# Zio_Qwiic_PM2_5_Sensor_Adapter.net
KiCad netlist of a schematic drawn in EAGLE
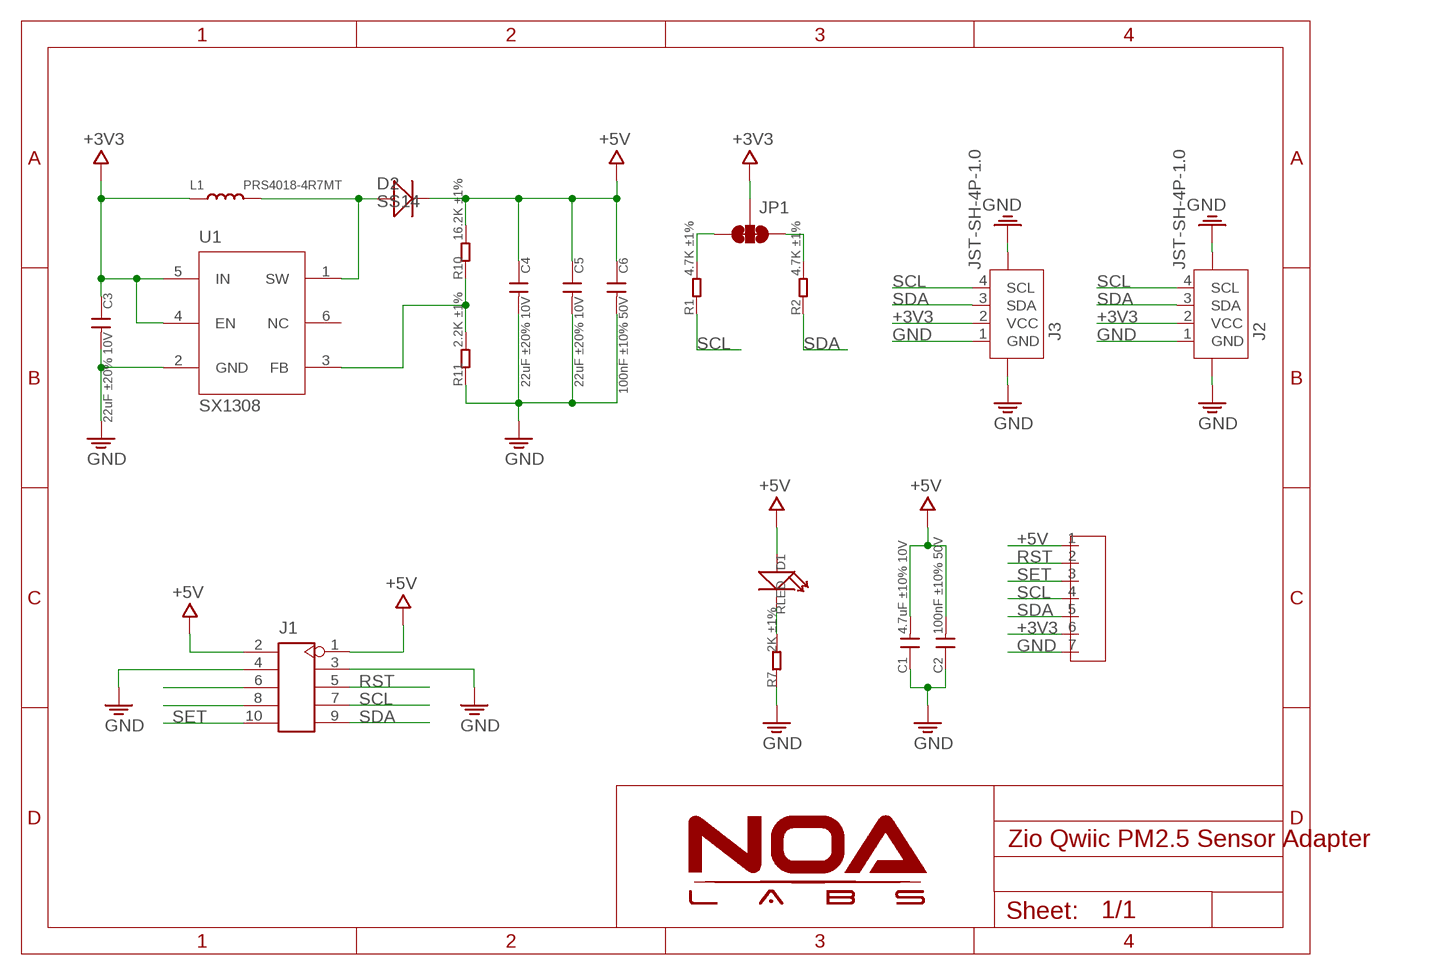
[diagram p0: schematic, sheet 1]

(export (version "E")
  (design (tool "Eeschema 10.0.6"))
  (components
    (comp (ref "C1")
      (value "4.7uF ±10% 10V")
      (footprint "eagle-import:C0603")
      (libsource (lib "eagle-import") (part "C-0603"))
    )
    (comp (ref "C2")
      (value "100nF ±10% 50V")
      (footprint "eagle-import:C0603")
      (libsource (lib "eagle-import") (part "C-0603"))
    )
    (comp (ref "C3")
      (value "22uF ±20% 10V")
      (footprint "eagle-import:C0805")
      (libsource (lib "eagle-import") (part "C-0805"))
    )
    (comp (ref "C4")
      (value "22uF ±20% 10V")
      (footprint "eagle-import:C0805")
      (libsource (lib "eagle-import") (part "C-0805"))
    )
    (comp (ref "C5")
      (value "22uF ±20% 10V")
      (footprint "eagle-import:C0805")
      (libsource (lib "eagle-import") (part "C-0805"))
    )
    (comp (ref "C6")
      (value "100nF ±10% 50V")
      (footprint "eagle-import:C0603")
      (libsource (lib "eagle-import") (part "C-0603"))
    )
    (comp (ref "D1")
      (value "RLED")
      (footprint "eagle-import:LED-0603")
      (libsource (lib "eagle-import") (part "LED'0603'"))
    )
    (comp (ref "D2")
      (value "SS14")
      (footprint "eagle-import:DO-214AC")
      (libsource (lib "eagle-import") (part "D214AA"))
    )
    (comp (ref "J1")
      (value "HEADER-2X5P-PM2.5")
      (footprint "eagle-import:2X5P-1.27-THT-PM2.5")
      (libsource (lib "eagle-import") (part "HEADER-2X5P-PM2.5"))
    )
    (comp (ref "J2")
      (value "JST-SH-4P-1.0")
      (footprint "eagle-import:JST-SH-4P")
      (libsource (lib "eagle-import") (part "JST-SH-4P-1.0"))
    )
    (comp (ref "J3")
      (value "JST-SH-4P-1.0")
      (footprint "eagle-import:JST-SH-4P")
      (libsource (lib "eagle-import") (part "JST-SH-4P-1.0"))
    )
    (comp (ref "J5")
      (value "HEADER-7P")
      (footprint "eagle-import:7P-2.54-60_35MIL")
      (libsource (lib "eagle-import") (part "HEADER-7P"))
    )
    (comp (ref "JP1")
      (value "SMT-JUMPER_3_2-NC_TRACE")
      (footprint "eagle-import:SMT-JUMPER_3_2-NC_TRACE")
      (libsource (lib "eagle-import") (part "SMT-JUMPER_3_2-NC_TRACE"))
    )
    (comp (ref "L1")
      (value "PRS4018-4R7MT")
      (footprint "eagle-import:L4030")
      (libsource (lib "eagle-import") (part "L-4030"))
    )
    (comp (ref "R1")
      (value "4.7K ±1%")
      (footprint "eagle-import:R0603")
      (libsource (lib "eagle-import") (part "RCL_1838970_R-0603"))
    )
    (comp (ref "R2")
      (value "4.7K ±1%")
      (footprint "eagle-import:R0603")
      (libsource (lib "eagle-import") (part "RCL_1838970_R-0603"))
    )
    (comp (ref "R7")
      (value "2K ±1%")
      (footprint "eagle-import:0603")
      (libsource (lib "eagle-import") (part "R-0603"))
    )
    (comp (ref "R10")
      (value "16.2K ±1%")
      (footprint "eagle-import:R0603")
      (libsource (lib "eagle-import") (part "RCL_1838970_R-0603"))
    )
    (comp (ref "R11")
      (value "2.2K ±1%")
      (footprint "eagle-import:R0603")
      (libsource (lib "eagle-import") (part "RCL_1838970_R-0603"))
    )
    (comp (ref "U1")
      (value "SX1308")
      (footprint "eagle-import:SOT23-6")
      (libsource (lib "eagle-import") (part "SX1308"))
    )
  )
  (nets
    (net (code "1") (name "+3V3") (class "Default")
      (node (ref "C3") (pin "1") (pinfunction "1_1") (pintype "passive"))
      (node (ref "J2") (pin "2") (pinfunction "VCC_2") (pintype "bidirectional"))
      (node (ref "J3") (pin "2") (pinfunction "VCC_2") (pintype "bidirectional"))
      (node (ref "J5") (pin "6") (pinfunction "P$6_6") (pintype "bidirectional"))
      (node (ref "JP1") (pin "2") (pinfunction "2_2") (pintype "passive"))
      (node (ref "L1") (pin "1") (pinfunction "1_1") (pintype "passive"))
      (node (ref "U1") (pin "4") (pinfunction "EN_4") (pintype "bidirectional"))
      (node (ref "U1") (pin "5") (pinfunction "IN_5") (pintype "bidirectional"))
    )
    (net (code "2") (name "+5V") (class "Default")
      (node (ref "C1") (pin "2") (pinfunction "2_2") (pintype "passive"))
      (node (ref "C2") (pin "2") (pinfunction "2_2") (pintype "passive"))
      (node (ref "C4") (pin "1") (pinfunction "1_1") (pintype "passive"))
      (node (ref "C5") (pin "1") (pinfunction "1_1") (pintype "passive"))
      (node (ref "C6") (pin "1") (pinfunction "1_1") (pintype "passive"))
      (node (ref "D1") (pin "+") (pinfunction "+_+") (pintype "passive"))
      (node (ref "D2") (pin "C") (pinfunction "-_C") (pintype "passive"))
      (node (ref "J1") (pin "1") (pinfunction "1_1") (pintype "bidirectional"))
      (node (ref "J1") (pin "2") (pinfunction "2_2") (pintype "bidirectional"))
      (node (ref "J5") (pin "1") (pinfunction "P$1_1") (pintype "bidirectional"))
      (node (ref "R10") (pin "2") (pinfunction "2_2") (pintype "passive"))
    )
    (net (code "3") (name "/RST") (class "Default")
      (node (ref "J1") (pin "5") (pinfunction "5_5") (pintype "bidirectional"))
      (node (ref "J5") (pin "2") (pinfunction "P$2_2") (pintype "bidirectional"))
    )
    (net (code "4") (name "/SCL") (class "Default")
      (node (ref "J1") (pin "7") (pinfunction "7_7") (pintype "bidirectional"))
      (node (ref "J2") (pin "4") (pinfunction "SCL_4") (pintype "bidirectional"))
      (node (ref "J3") (pin "4") (pinfunction "SCL_4") (pintype "bidirectional"))
      (node (ref "J5") (pin "4") (pinfunction "P$4_4") (pintype "bidirectional"))
      (node (ref "R1") (pin "1") (pinfunction "1_1") (pintype "passive"))
    )
    (net (code "5") (name "/SDA") (class "Default")
      (node (ref "J1") (pin "9") (pinfunction "9_9") (pintype "bidirectional"))
      (node (ref "J2") (pin "3") (pinfunction "SDA_3") (pintype "bidirectional"))
      (node (ref "J3") (pin "3") (pinfunction "SDA_3") (pintype "bidirectional"))
      (node (ref "J5") (pin "5") (pinfunction "P$5_5") (pintype "bidirectional"))
      (node (ref "R2") (pin "1") (pinfunction "1_1") (pintype "passive"))
    )
    (net (code "6") (name "/SET") (class "Default")
      (node (ref "J1") (pin "10") (pinfunction "10_10") (pintype "bidirectional"))
      (node (ref "J5") (pin "3") (pinfunction "P$3_3") (pintype "bidirectional"))
    )
    (net (code "7") (name "GND") (class "Default")
      (node (ref "C1") (pin "1") (pinfunction "1_1") (pintype "passive"))
      (node (ref "C2") (pin "1") (pinfunction "1_1") (pintype "passive"))
      (node (ref "C3") (pin "2") (pinfunction "2_2") (pintype "passive"))
      (node (ref "C4") (pin "2") (pinfunction "2_2") (pintype "passive"))
      (node (ref "C5") (pin "2") (pinfunction "2_2") (pintype "passive"))
      (node (ref "C6") (pin "2") (pinfunction "2_2") (pintype "passive"))
      (node (ref "J1") (pin "3") (pinfunction "3_3") (pintype "bidirectional"))
      (node (ref "J1") (pin "4") (pinfunction "4_4") (pintype "bidirectional"))
      (node (ref "J2") (pin "1") (pinfunction "GND_1") (pintype "bidirectional"))
      (node (ref "J2") (pin "NC1") (pinfunction "5_NC1") (pintype "bidirectional"))
      (node (ref "J2") (pin "NC2") (pinfunction "6_NC2") (pintype "bidirectional"))
      (node (ref "J3") (pin "1") (pinfunction "GND_1") (pintype "bidirectional"))
      (node (ref "J3") (pin "NC1") (pinfunction "5_NC1") (pintype "bidirectional"))
      (node (ref "J3") (pin "NC2") (pinfunction "6_NC2") (pintype "bidirectional"))
      (node (ref "J5") (pin "7") (pinfunction "P$7_7") (pintype "bidirectional"))
      (node (ref "R11") (pin "1") (pinfunction "1_1") (pintype "passive"))
      (node (ref "R7") (pin "1") (pinfunction "1_1") (pintype "passive"))
      (node (ref "U1") (pin "2") (pinfunction "GND_2") (pintype "bidirectional"))
    )
    (net (code "8") (name "Net-(D1-Pad-)") (class "Default")
      (node (ref "D1") (pin "-") (pinfunction "-_-") (pintype "passive"))
      (node (ref "R7") (pin "2") (pinfunction "2_2") (pintype "passive"))
    )
    (net (code "9") (name "Net-(D2-+)") (class "Default")
      (node (ref "D2") (pin "A") (pinfunction "+_A") (pintype "passive"))
      (node (ref "L1") (pin "2") (pinfunction "2_2") (pintype "passive"))
      (node (ref "U1") (pin "1") (pinfunction "SW_1") (pintype "bidirectional"))
    )
    (net (code "10") (name "Net-(JP1-Pad1)") (class "Default")
      (node (ref "JP1") (pin "1") (pinfunction "1_1") (pintype "passive"))
      (node (ref "R2") (pin "2") (pinfunction "2_2") (pintype "passive"))
    )
    (net (code "11") (name "Net-(JP1-Pad3)") (class "Default")
      (node (ref "JP1") (pin "3") (pinfunction "3_3") (pintype "passive"))
      (node (ref "R1") (pin "2") (pinfunction "2_2") (pintype "passive"))
    )
    (net (code "12") (name "Net-(U1-FB)") (class "Default")
      (node (ref "R10") (pin "1") (pinfunction "1_1") (pintype "passive"))
      (node (ref "R11") (pin "2") (pinfunction "2_2") (pintype "passive"))
      (node (ref "U1") (pin "3") (pinfunction "FB_3") (pintype "bidirectional"))
    )
    (net (code "13") (name "unconnected-(J1-Pad6)") (class "Default")
      (node (ref "J1") (pin "6") (pinfunction "6_6") (pintype "bidirectional"))
    )
    (net (code "14") (name "unconnected-(J1-Pad8)") (class "Default")
      (node (ref "J1") (pin "8") (pinfunction "8_8") (pintype "bidirectional"))
    )
    (net (code "15") (name "unconnected-(U1-NC-Pad6)") (class "Default")
      (node (ref "U1") (pin "6") (pinfunction "NC_6") (pintype "bidirectional"))
    )
  )
)
